# Sheet1.net
KiCad netlist of a schematic drawn in Altium Designer
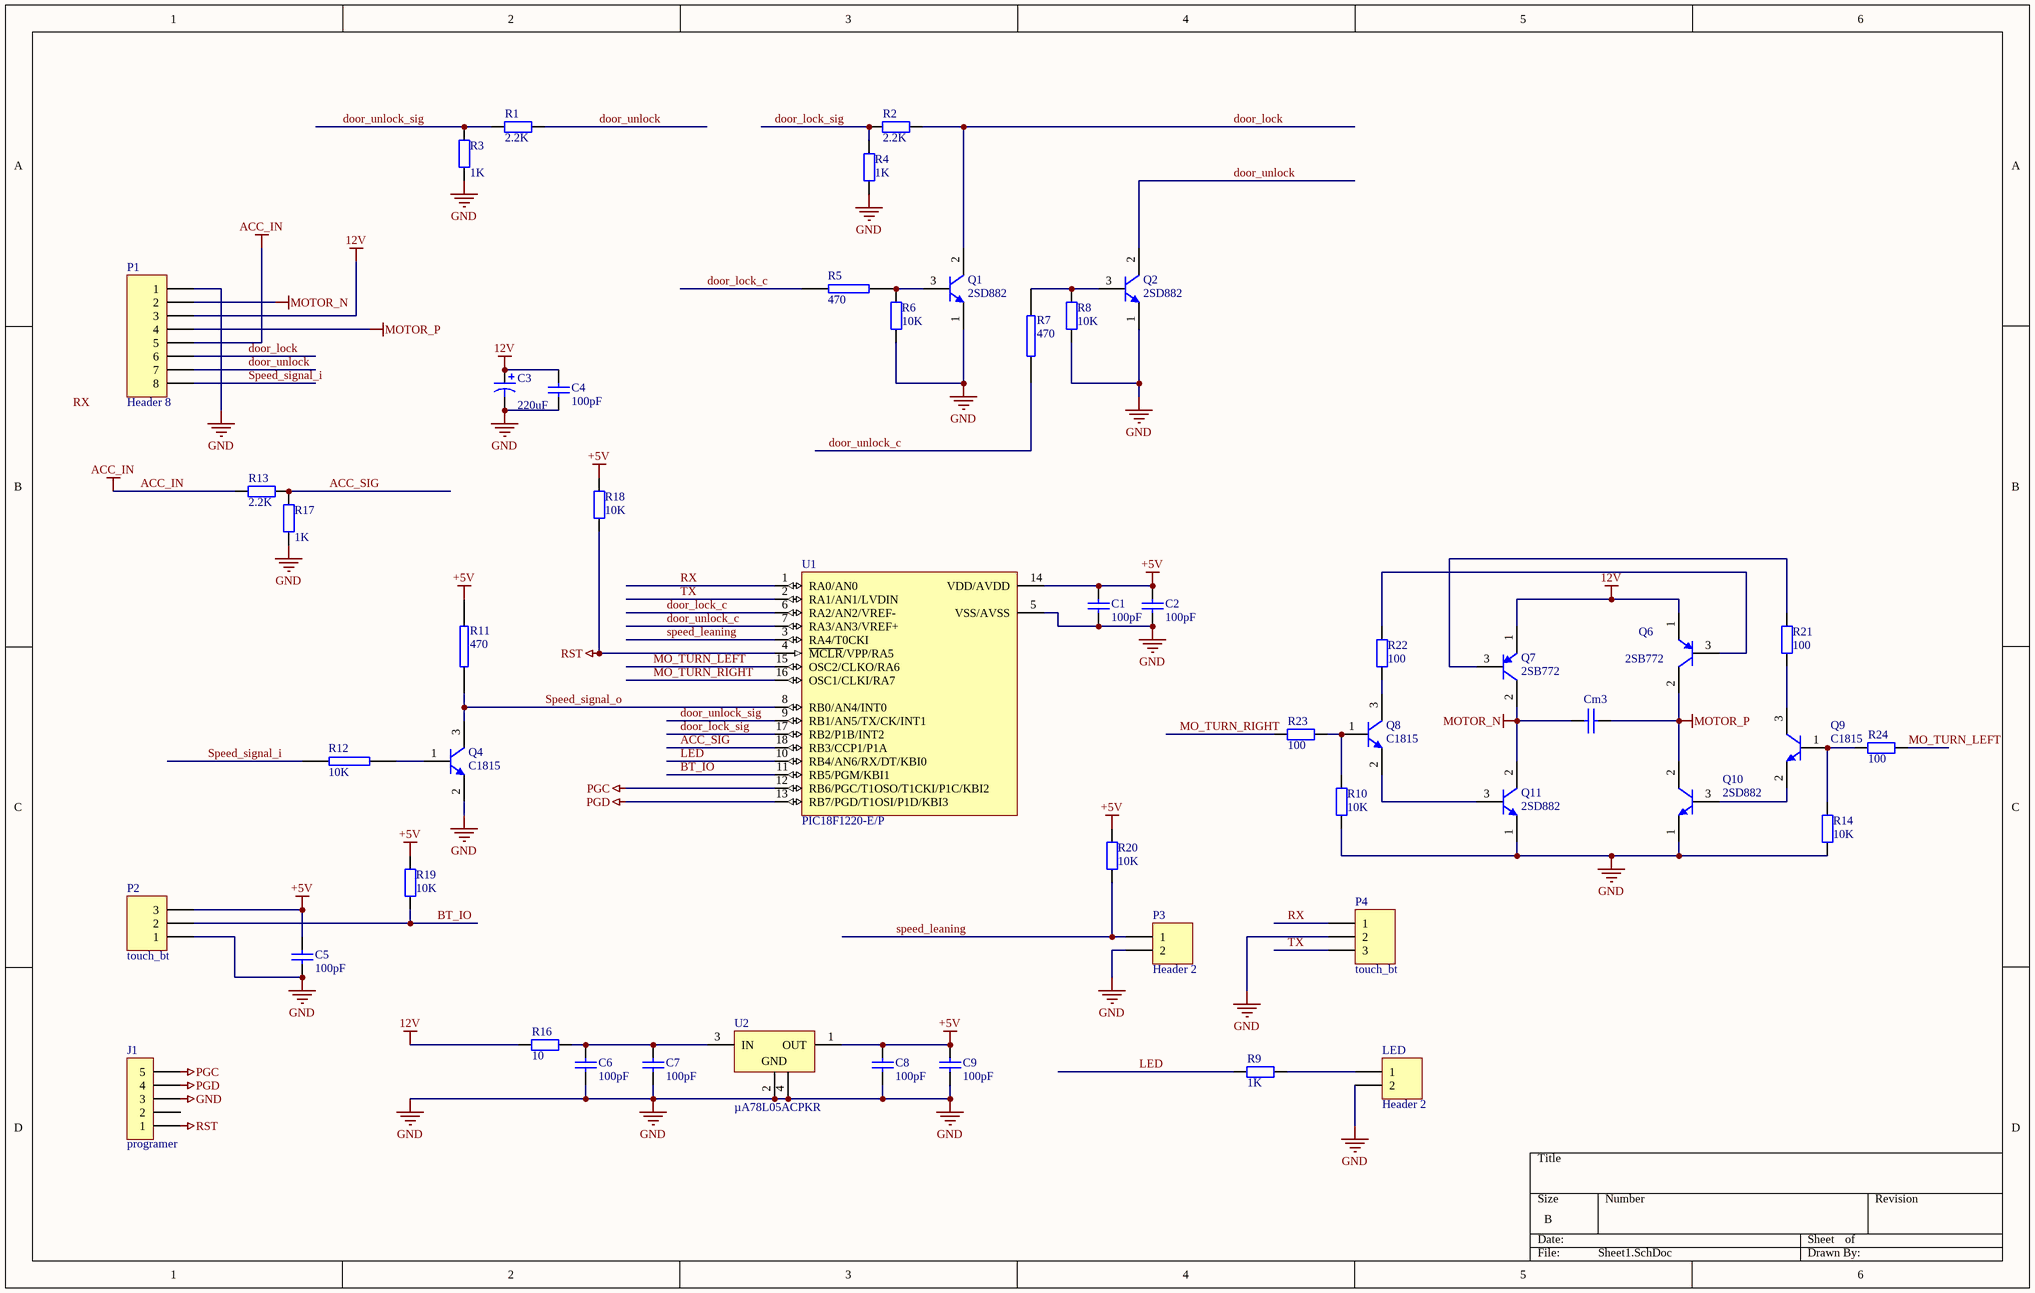
[diagram p0: Sheet1.SchDoc]

(export (version "E")
  (design (tool "Eeschema 10.0.6"))
  (components
    (comp (ref "C1")
      (value "100pF")
      (footprint "RESC2012L")
      (description "Capacitor (Semiconductor SIM Model)")
      (fields (field (name "Comment") "Cap Semi") (field (name "PUBLISHER") "Altium Limited"))
      (libsource (lib "Miscellaneous Devices") (part "Cap Semi"))
    )
    (comp (ref "C2")
      (value "100pF")
      (footprint "RESC2012L")
      (description "Capacitor (Semiconductor SIM Model)")
      (fields (field (name "Comment") "Cap Semi") (field (name "PUBLISHER") "Altium Limited"))
      (libsource (lib "Miscellaneous Devices") (part "Cap Semi"))
    )
    (comp (ref "C3")
      (value "220uF")
      (footprint "CAPU150-175K")
      (description "Polarized Capacitor (Surface Mount)")
      (fields (field (name "Comment") "Cap Pol3") (field (name "PUBLISHER") "Altium Limited"))
      (libsource (lib "Miscellaneous Devices") (part "Cap Pol3"))
    )
    (comp (ref "C4")
      (value "100pF")
      (footprint "RESC2012L")
      (description "Capacitor (Semiconductor SIM Model)")
      (fields (field (name "Comment") "Cap Semi") (field (name "PUBLISHER") "Altium Limited"))
      (libsource (lib "Miscellaneous Devices") (part "Cap Semi"))
    )
    (comp (ref "C5")
      (value "100pF")
      (footprint "RESC2012L")
      (description "Capacitor (Semiconductor SIM Model)")
      (fields (field (name "Comment") "Cap Semi") (field (name "PUBLISHER") "Altium Limited"))
      (libsource (lib "Miscellaneous Devices") (part "Cap Semi"))
    )
    (comp (ref "C6")
      (value "100pF")
      (footprint "RESC2012L")
      (description "Capacitor (Semiconductor SIM Model)")
      (fields (field (name "Comment") "Cap Semi") (field (name "PUBLISHER") "Altium Limited"))
      (libsource (lib "Miscellaneous Devices") (part "Cap Semi"))
    )
    (comp (ref "C7")
      (value "100pF")
      (footprint "RESC2012L")
      (description "Capacitor (Semiconductor SIM Model)")
      (fields (field (name "Comment") "Cap Semi") (field (name "PUBLISHER") "Altium Limited"))
      (libsource (lib "Miscellaneous Devices") (part "Cap Semi"))
    )
    (comp (ref "C8")
      (value "100pF")
      (footprint "RESC2012L")
      (description "Capacitor (Semiconductor SIM Model)")
      (fields (field (name "Comment") "Cap Semi") (field (name "PUBLISHER") "Altium Limited"))
      (libsource (lib "Miscellaneous Devices") (part "Cap Semi"))
    )
    (comp (ref "C9")
      (value "100pF")
      (footprint "RESC2012L")
      (description "Capacitor (Semiconductor SIM Model)")
      (fields (field (name "Comment") "Cap Semi") (field (name "PUBLISHER") "Altium Limited"))
      (libsource (lib "Miscellaneous Devices") (part "Cap Semi"))
    )
    (comp (ref "Cm3")
      (value "~")
      (footprint "1206")
      (description "Capacitor")
      (libsource (lib "*") (part "CAP"))
    )
    (comp (ref "J1")
      (value "programer")
      (footprint "HDR1x5")
      (description "Connector")
      (libsource (lib "*") (part "CON5"))
    )
    (comp (ref "LED")
      (value "Header 2")
      (footprint "HDR1X2")
      (description "Header, 2-Pin")
      (fields (field (name "PUBLISHER") "Altium Limited"))
      (libsource (lib "Miscellaneous Connectors") (part "Header 2"))
    )
    (comp (ref "P1")
      (value "Header 8")
      (footprint "P8_150")
      (description "Header, 8-Pin")
      (fields (field (name "PUBLISHER") "Altium Limited"))
      (libsource (lib "Miscellaneous Connectors") (part "Header 8"))
    )
    (comp (ref "P2")
      (value "touch_bt")
      (footprint "HDR1X3")
      (description "Header, 3-Pin")
      (fields (field (name "PUBLISHER") "Altium Limited"))
      (libsource (lib "Miscellaneous Connectors") (part "Header 3"))
    )
    (comp (ref "P3")
      (value "Header 2")
      (footprint "HDR1X2")
      (description "Header, 2-Pin")
      (fields (field (name "PUBLISHER") "Altium Limited"))
      (libsource (lib "Miscellaneous Connectors") (part "Header 2"))
    )
    (comp (ref "P4")
      (value "touch_bt")
      (footprint "HDR1X3")
      (description "Header, 3-Pin")
      (fields (field (name "PUBLISHER") "Altium Limited"))
      (libsource (lib "") (part "Header 3_1"))
    )
    (comp (ref "Q1")
      (value "2SD882")
      (footprint "ONSC-TO-225-3-77-09")
      (description "Plastic Medium-Power NPN Silicon Transistor, 3-Pin TO-225, Bulk Box")
      (fields (field (name "MANUFACTURER") "On Semiconductor") (field (name "PARTNUMBER") "MJE340"))
      (libsource (lib "ON Semi General Purpose Transistors") (part "MJE340"))
    )
    (comp (ref "Q2")
      (value "2SD882")
      (footprint "ONSC-TO-225-3-77-09")
      (description "Plastic Medium-Power NPN Silicon Transistor, 3-Pin TO-225, Bulk Box")
      (fields (field (name "MANUFACTURER") "On Semiconductor") (field (name "PARTNUMBER") "MJE340"))
      (libsource (lib "ON Semi General Purpose Transistors") (part "MJE340"))
    )
    (comp (ref "Q4")
      (value "C1815")
      (footprint "ONSC-CPA-3_V")
      (description "Bipolar Transistor, 50 V, 150 mA, Low VCE(sat), NPN Single, 3-Pin CPA, Pb-Free, Tape and Reel")
      (fields
        (field (name "MANUFACTURER") "On Semiconductor")
        (field (name "PARTNUMBER") "2SC2812N6-CPA-TB-E")
      )
      (libsource (lib "ON Semi General Purpose Transistors") (part "2SC2812N6-CPA-TB-E"))
    )
    (comp (ref "Q6")
      (value "2SB772")
      (footprint "ONSC-TO-225-3-77-09")
      (description "Plastic Medium-Power PNP Silicon Transistor, 3-Pin TO-225, Bulk Box")
      (fields (field (name "MANUFACTURER") "On Semiconductor") (field (name "PARTNUMBER") "MJE350"))
      (libsource (lib "ON Semi General Purpose Transistors") (part "MJE350"))
    )
    (comp (ref "Q7")
      (value "2SB772")
      (footprint "ONSC-TO-225-3-77-09")
      (description "Plastic Medium-Power PNP Silicon Transistor, 3-Pin TO-225, Bulk Box")
      (fields (field (name "MANUFACTURER") "On Semiconductor") (field (name "PARTNUMBER") "MJE350"))
      (libsource (lib "ON Semi General Purpose Transistors") (part "MJE350"))
    )
    (comp (ref "Q8")
      (value "C1815")
      (footprint "ONSC-CPA-3_V")
      (description "Bipolar Transistor, 50 V, 150 mA, Low VCE(sat), NPN Single, 3-Pin CPA, Pb-Free, Tape and Reel")
      (fields
        (field (name "MANUFACTURER") "On Semiconductor")
        (field (name "PARTNUMBER") "2SC2812N6-CPA-TB-E")
      )
      (libsource (lib "ON Semi General Purpose Transistors") (part "2SC2812N6-CPA-TB-E"))
    )
    (comp (ref "Q9")
      (value "C1815")
      (footprint "ONSC-CPA-3_V")
      (description "Bipolar Transistor, 50 V, 150 mA, Low VCE(sat), NPN Single, 3-Pin CPA, Pb-Free, Tape and Reel")
      (fields
        (field (name "MANUFACTURER") "On Semiconductor")
        (field (name "PARTNUMBER") "2SC2812N6-CPA-TB-E")
      )
      (libsource (lib "ON Semi General Purpose Transistors") (part "2SC2812N6-CPA-TB-E"))
    )
    (comp (ref "Q10")
      (value "2SD882")
      (footprint "ONSC-TO-225-3-77-09")
      (description "Plastic Medium-Power NPN Silicon Transistor, 3-Pin TO-225, Bulk Box")
      (fields (field (name "MANUFACTURER") "On Semiconductor") (field (name "PARTNUMBER") "MJE340"))
      (libsource (lib "ON Semi General Purpose Transistors") (part "MJE340"))
    )
    (comp (ref "Q11")
      (value "2SD882")
      (footprint "ONSC-TO-225-3-77-09")
      (description "Plastic Medium-Power NPN Silicon Transistor, 3-Pin TO-225, Bulk Box")
      (fields (field (name "MANUFACTURER") "On Semiconductor") (field (name "PARTNUMBER") "MJE340"))
      (libsource (lib "ON Semi General Purpose Transistors") (part "MJE340"))
    )
    (comp (ref "R1")
      (value "2.2K")
      (footprint "RESC2012L")
      (description "Resistor")
      (fields (field (name "Comment") "Res2") (field (name "PUBLISHER") "Altium Limited"))
      (libsource (lib "") (part "Res2_1"))
    )
    (comp (ref "R2")
      (value "2.2K")
      (footprint "RESC2012L")
      (description "Resistor")
      (fields (field (name "Comment") "Res2") (field (name "PUBLISHER") "Altium Limited"))
      (libsource (lib "") (part "Res2_1"))
    )
    (comp (ref "R3")
      (value "1K")
      (footprint "RESC2012L")
      (description "Resistor")
      (fields (field (name "Comment") "Res2") (field (name "PUBLISHER") "Altium Limited"))
      (libsource (lib "") (part "Res2_2"))
    )
    (comp (ref "R4")
      (value "1K")
      (footprint "RESC2012L")
      (description "Resistor")
      (fields (field (name "Comment") "Res2") (field (name "PUBLISHER") "Altium Limited"))
      (libsource (lib "Miscellaneous Devices") (part "Res2"))
    )
    (comp (ref "R5") (value "470") (footprint "RESC2012L") (libsource (lib "*") (part "RES2")))
    (comp (ref "R6")
      (value "10K")
      (footprint "RESC2012L")
      (description "Resistor")
      (fields (field (name "Comment") "Res2") (field (name "PUBLISHER") "Altium Limited"))
      (libsource (lib "Miscellaneous Devices") (part "Res2"))
    )
    (comp (ref "R7") (value "470") (footprint "RESC2012L") (libsource (lib "*") (part "RES2")))
    (comp (ref "R8")
      (value "10K")
      (footprint "RESC2012L")
      (description "Resistor")
      (fields (field (name "Comment") "Res2") (field (name "PUBLISHER") "Altium Limited"))
      (libsource (lib "Miscellaneous Devices") (part "Res2"))
    )
    (comp (ref "R9")
      (value "1K")
      (footprint "RESC2012L")
      (description "Resistor")
      (fields (field (name "Comment") "Res2") (field (name "PUBLISHER") "Altium Limited"))
      (libsource (lib "") (part "Res2_1"))
    )
    (comp (ref "R10")
      (value "10K")
      (footprint "RESC2012L")
      (description "Resistor")
      (fields (field (name "Comment") "Res2") (field (name "PUBLISHER") "Altium Limited"))
      (libsource (lib "Miscellaneous Devices") (part "Res2"))
    )
    (comp (ref "R11") (value "470") (footprint "RESC2012L") (libsource (lib "*") (part "RES2")))
    (comp (ref "R12") (value "10K") (footprint "RESC2012L") (libsource (lib "*") (part "RES2")))
    (comp (ref "R13")
      (value "2.2K")
      (footprint "RESC2012L")
      (description "Resistor")
      (fields (field (name "Comment") "Res2") (field (name "PUBLISHER") "Altium Limited"))
      (libsource (lib "") (part "Res2_1"))
    )
    (comp (ref "R14")
      (value "10K")
      (footprint "RESC2012L")
      (description "Resistor")
      (fields (field (name "Comment") "Res2") (field (name "PUBLISHER") "Altium Limited"))
      (libsource (lib "Miscellaneous Devices") (part "Res2"))
    )
    (comp (ref "R16")
      (value "10")
      (footprint "1206")
      (description "Resistor")
      (fields (field (name "Comment") "Res2") (field (name "PUBLISHER") "Altium Limited"))
      (libsource (lib "") (part "Res2_1"))
    )
    (comp (ref "R17")
      (value "1K")
      (footprint "RESC2012L")
      (description "Resistor")
      (fields (field (name "Comment") "Res2") (field (name "PUBLISHER") "Altium Limited"))
      (libsource (lib "") (part "Res2_2"))
    )
    (comp (ref "R18")
      (value "10K")
      (footprint "RESC2012L")
      (description "Resistor")
      (fields (field (name "Comment") "Res2") (field (name "PUBLISHER") "Altium Limited"))
      (libsource (lib "Miscellaneous Devices") (part "Res2"))
    )
    (comp (ref "R19")
      (value "10K")
      (footprint "RESC2012L")
      (description "Resistor")
      (fields (field (name "Comment") "Res2") (field (name "PUBLISHER") "Altium Limited"))
      (libsource (lib "Miscellaneous Devices") (part "Res2"))
    )
    (comp (ref "R20")
      (value "10K")
      (footprint "RESC2012L")
      (description "Resistor")
      (fields (field (name "Comment") "Res2") (field (name "PUBLISHER") "Altium Limited"))
      (libsource (lib "Miscellaneous Devices") (part "Res2"))
    )
    (comp (ref "R21")
      (value "100")
      (footprint "RESC2012L")
      (description "Resistor")
      (fields (field (name "Comment") "Res2") (field (name "PUBLISHER") "Altium Limited"))
      (libsource (lib "Miscellaneous Devices") (part "Res2"))
    )
    (comp (ref "R22")
      (value "100")
      (footprint "RESC2012L")
      (description "Resistor")
      (fields (field (name "Comment") "Res2") (field (name "PUBLISHER") "Altium Limited"))
      (libsource (lib "Miscellaneous Devices") (part "Res2"))
    )
    (comp (ref "R23")
      (value "100")
      (footprint "RESC2012L")
      (description "Resistor")
      (fields (field (name "Comment") "Res2") (field (name "PUBLISHER") "Altium Limited"))
      (libsource (lib "") (part "Res2_3"))
    )
    (comp (ref "R24")
      (value "100")
      (footprint "RESC2012L")
      (description "Resistor")
      (fields (field (name "Comment") "Res2") (field (name "PUBLISHER") "Altium Limited"))
      (libsource (lib "") (part "Res2_3"))
    )
    (comp (ref "U1")
      (value "PIC18F1220-E/P")
      (footprint "PDIP300-P18")
      (fields (field (name "PUBLISHER") "Altium Limited"))
      (libsource (lib "Microchip Microcontroller 8-Bit PIC18") (part "PIC18F1220-E/P"))
    )
    (comp (ref "U2")
      (value "µA78L05ACPKR")
      (footprint "PK03")
      (description "Positive-Voltage Regulator")
      (fields (field (name "PUBLISHER") "Altium Limited"))
      (libsource (lib "Schlib1") (part "µA78L05ACPKR"))
    )
  )
  (nets
    (net (code "1") (name "+5V") (class "Default")
      (node (ref "C1") (pin "2") (pinfunction "2_2") (pintype "passive"))
      (node (ref "C2") (pin "2") (pinfunction "2_2") (pintype "passive"))
      (node (ref "C5") (pin "2") (pinfunction "2_2") (pintype "passive"))
      (node (ref "C8") (pin "2") (pinfunction "2_2") (pintype "passive"))
      (node (ref "C9") (pin "2") (pinfunction "2_2") (pintype "passive"))
      (node (ref "P2") (pin "3") (pinfunction "3_3") (pintype "passive"))
      (node (ref "R11") (pin "1") (pinfunction "1_1") (pintype "passive"))
      (node (ref "R18") (pin "1") (pinfunction "1_1") (pintype "passive"))
      (node (ref "R19") (pin "1") (pinfunction "1_1") (pintype "passive"))
      (node (ref "R20") (pin "1") (pinfunction "1_1") (pintype "passive"))
      (node (ref "U1") (pin "14") (pinfunction "VDD/AVDD_14") (pintype "power_in"))
      (node (ref "U2") (pin "1") (pinfunction "OUT_1") (pintype "power_in"))
    )
    (net (code "2") (name "/ACC_SIG") (class "Default")
      (node (ref "R13") (pin "1") (pinfunction "1_1") (pintype "passive"))
      (node (ref "R17") (pin "2") (pinfunction "2_2") (pintype "passive"))
      (node (ref "U1") (pin "18") (pinfunction "RB3/CCP1/P1A_18") (pintype "bidirectional"))
    )
    (net (code "3") (name "/BT_IO") (class "Default")
      (node (ref "P2") (pin "2") (pinfunction "2_2") (pintype "passive"))
      (node (ref "R19") (pin "2") (pinfunction "2_2") (pintype "passive"))
      (node (ref "U1") (pin "11") (pinfunction "RB5/PGM/KBI1_11") (pintype "bidirectional"))
    )
    (net (code "4") (name "/LED") (class "Default")
      (node (ref "R9") (pin "2") (pinfunction "2_2") (pintype "passive"))
      (node (ref "U1") (pin "10") (pinfunction "RB4/AN6/RX/DT/KBI0_10") (pintype "bidirectional"))
    )
    (net (code "5") (name "/MO_TURN_LEFT") (class "Default")
      (node (ref "R24") (pin "2") (pinfunction "2_2") (pintype "passive"))
      (node (ref "U1") (pin "15") (pinfunction "OSC2/CLKO/RA6_15") (pintype "bidirectional"))
    )
    (net (code "6") (name "/MO_TURN_RIGHT") (class "Default")
      (node (ref "R23") (pin "1") (pinfunction "1_1") (pintype "passive"))
      (node (ref "U1") (pin "16") (pinfunction "OSC1/CLKI/RA7_16") (pintype "bidirectional"))
    )
    (net (code "7") (name "/RX") (class "Default")
      (node (ref "P4") (pin "1") (pinfunction "1_1") (pintype "passive"))
      (node (ref "U1") (pin "1") (pinfunction "RA0/AN0_1") (pintype "bidirectional"))
    )
    (net (code "8") (name "/Speed_signal_i") (class "Default")
      (node (ref "P1") (pin "8") (pinfunction "8_8") (pintype "passive"))
      (node (ref "R12") (pin "1") (pinfunction "1_1") (pintype "passive"))
    )
    (net (code "9") (name "/Speed_signal_o") (class "Default")
      (node (ref "Q4") (pin "3") (pinfunction "C_3") (pintype "passive"))
      (node (ref "R11") (pin "2") (pinfunction "2_2") (pintype "passive"))
      (node (ref "U1") (pin "8") (pinfunction "RB0/AN4/INT0_8") (pintype "bidirectional"))
    )
    (net (code "10") (name "/TX") (class "Default")
      (node (ref "P4") (pin "3") (pinfunction "3_3") (pintype "passive"))
      (node (ref "U1") (pin "2") (pinfunction "RA1/AN1/LVDIN_2") (pintype "bidirectional"))
    )
    (net (code "11") (name "/door_lock") (class "Default")
      (node (ref "P1") (pin "6") (pinfunction "6_6") (pintype "passive"))
      (node (ref "Q1") (pin "2") (pinfunction "C_2") (pintype "passive"))
      (node (ref "R2") (pin "1") (pinfunction "1_1") (pintype "passive"))
    )
    (net (code "12") (name "/door_lock_c") (class "Default")
      (node (ref "R5") (pin "1") (pinfunction "1_1") (pintype "passive"))
      (node (ref "U1") (pin "6") (pinfunction "RA2/AN2/VREF-_6") (pintype "bidirectional"))
    )
    (net (code "13") (name "/door_lock_sig") (class "Default")
      (node (ref "R2") (pin "2") (pinfunction "2_2") (pintype "passive"))
      (node (ref "R4") (pin "1") (pinfunction "1_1") (pintype "passive"))
      (node (ref "U1") (pin "17") (pinfunction "RB2/P1B/INT2_17") (pintype "bidirectional"))
    )
    (net (code "14") (name "/door_unlock") (class "Default")
      (node (ref "P1") (pin "7") (pinfunction "7_7") (pintype "passive"))
      (node (ref "Q2") (pin "2") (pinfunction "C_2") (pintype "passive"))
      (node (ref "R1") (pin "1") (pinfunction "1_1") (pintype "passive"))
    )
    (net (code "15") (name "/door_unlock_c") (class "Default")
      (node (ref "R7") (pin "2") (pinfunction "2_2") (pintype "passive"))
      (node (ref "U1") (pin "7") (pinfunction "RA3/AN3/VREF+_7") (pintype "bidirectional"))
    )
    (net (code "16") (name "/door_unlock_sig") (class "Default")
      (node (ref "R1") (pin "2") (pinfunction "2_2") (pintype "passive"))
      (node (ref "R3") (pin "2") (pinfunction "2_2") (pintype "passive"))
      (node (ref "U1") (pin "9") (pinfunction "RB1/AN5/TX/CK/INT1_9") (pintype "bidirectional"))
    )
    (net (code "17") (name "/speed_leaning") (class "Default")
      (node (ref "P3") (pin "1") (pinfunction "1_1") (pintype "passive"))
      (node (ref "R20") (pin "2") (pinfunction "2_2") (pintype "passive"))
      (node (ref "U1") (pin "3") (pinfunction "RA4/T0CKI_3") (pintype "bidirectional"))
    )
    (net (code "18") (name "12V") (class "Default")
      (node (ref "C3") (pin "1") (pinfunction "1_1") (pintype "passive"))
      (node (ref "C4") (pin "2") (pinfunction "2_2") (pintype "passive"))
      (node (ref "P1") (pin "3") (pinfunction "3_3") (pintype "passive"))
      (node (ref "Q6") (pin "1") (pinfunction "E_1") (pintype "passive"))
      (node (ref "Q7") (pin "1") (pinfunction "E_1") (pintype "passive"))
      (node (ref "R16") (pin "2") (pinfunction "2_2") (pintype "passive"))
    )
    (net (code "19") (name "ACC_IN") (class "Default")
      (node (ref "P1") (pin "5") (pinfunction "5_5") (pintype "passive"))
      (node (ref "R13") (pin "2") (pinfunction "2_2") (pintype "passive"))
    )
    (net (code "20") (name "GND") (class "Default")
      (node (ref "C1") (pin "1") (pinfunction "1_1") (pintype "passive"))
      (node (ref "C2") (pin "1") (pinfunction "1_1") (pintype "passive"))
      (node (ref "C3") (pin "2") (pinfunction "2_2") (pintype "passive"))
      (node (ref "C4") (pin "1") (pinfunction "1_1") (pintype "passive"))
      (node (ref "C5") (pin "1") (pinfunction "1_1") (pintype "passive"))
      (node (ref "C6") (pin "1") (pinfunction "1_1") (pintype "passive"))
      (node (ref "C7") (pin "1") (pinfunction "1_1") (pintype "passive"))
      (node (ref "C8") (pin "1") (pinfunction "1_1") (pintype "passive"))
      (node (ref "C9") (pin "1") (pinfunction "1_1") (pintype "passive"))
      (node (ref "J1") (pin "3") (pinfunction "3_3") (pintype "passive"))
      (node (ref "LED") (pin "2") (pinfunction "2_2") (pintype "passive"))
      (node (ref "P1") (pin "1") (pinfunction "1_1") (pintype "passive"))
      (node (ref "P2") (pin "1") (pinfunction "1_1") (pintype "passive"))
      (node (ref "P3") (pin "2") (pinfunction "2_2") (pintype "passive"))
      (node (ref "P4") (pin "2") (pinfunction "2_2") (pintype "passive"))
      (node (ref "Q1") (pin "1") (pinfunction "E_1") (pintype "passive"))
      (node (ref "Q10") (pin "1") (pinfunction "E_1") (pintype "passive"))
      (node (ref "Q11") (pin "1") (pinfunction "E_1") (pintype "passive"))
      (node (ref "Q2") (pin "1") (pinfunction "E_1") (pintype "passive"))
      (node (ref "Q4") (pin "2") (pinfunction "E_2") (pintype "passive"))
      (node (ref "R10") (pin "2") (pinfunction "2_2") (pintype "passive"))
      (node (ref "R14") (pin "2") (pinfunction "2_2") (pintype "passive"))
      (node (ref "R17") (pin "1") (pinfunction "1_1") (pintype "passive"))
      (node (ref "R3") (pin "1") (pinfunction "1_1") (pintype "passive"))
      (node (ref "R4") (pin "2") (pinfunction "2_2") (pintype "passive"))
      (node (ref "R6") (pin "2") (pinfunction "2_2") (pintype "passive"))
      (node (ref "R8") (pin "2") (pinfunction "2_2") (pintype "passive"))
      (node (ref "U1") (pin "5") (pinfunction "VSS/AVSS_5") (pintype "power_in"))
      (node (ref "U2") (pin "2") (pinfunction "GND_2") (pintype "power_in"))
      (node (ref "U2") (pin "4") (pinfunction "GND_4") (pintype "power_in"))
    )
    (net (code "21") (name "MOTOR_N") (class "Default")
      (node (ref "Cm3") (pin "1") (pinfunction "1_1") (pintype "passive"))
      (node (ref "P1") (pin "2") (pinfunction "2_2") (pintype "passive"))
      (node (ref "Q11") (pin "2") (pinfunction "C_2") (pintype "passive"))
      (node (ref "Q7") (pin "2") (pinfunction "C_2") (pintype "passive"))
    )
    (net (code "22") (name "MOTOR_P") (class "Default")
      (node (ref "Cm3") (pin "2") (pinfunction "2_2") (pintype "passive"))
      (node (ref "P1") (pin "4") (pinfunction "4_4") (pintype "passive"))
      (node (ref "Q10") (pin "2") (pinfunction "C_2") (pintype "passive"))
      (node (ref "Q6") (pin "2") (pinfunction "C_2") (pintype "passive"))
    )
    (net (code "23") (name "Net-(LED-Pad1)") (class "Default")
      (node (ref "LED") (pin "1") (pinfunction "1_1") (pintype "passive"))
      (node (ref "R9") (pin "1") (pinfunction "1_1") (pintype "passive"))
    )
    (net (code "24") (name "Net-(Q1-B)") (class "Default")
      (node (ref "Q1") (pin "3") (pinfunction "B_3") (pintype "passive"))
      (node (ref "R5") (pin "2") (pinfunction "2_2") (pintype "passive"))
      (node (ref "R6") (pin "1") (pinfunction "1_1") (pintype "passive"))
    )
    (net (code "25") (name "Net-(Q2-B)") (class "Default")
      (node (ref "Q2") (pin "3") (pinfunction "B_3") (pintype "passive"))
      (node (ref "R7") (pin "1") (pinfunction "1_1") (pintype "passive"))
      (node (ref "R8") (pin "1") (pinfunction "1_1") (pintype "passive"))
    )
    (net (code "26") (name "Net-(Q4-B)") (class "Default")
      (node (ref "Q4") (pin "1") (pinfunction "B_1") (pintype "passive"))
      (node (ref "R12") (pin "2") (pinfunction "2_2") (pintype "passive"))
    )
    (net (code "27") (name "Net-(Q6-B)") (class "Default")
      (node (ref "Q6") (pin "3") (pinfunction "B_3") (pintype "passive"))
      (node (ref "R22") (pin "1") (pinfunction "1_1") (pintype "passive"))
    )
    (net (code "28") (name "Net-(Q7-B)") (class "Default")
      (node (ref "Q7") (pin "3") (pinfunction "B_3") (pintype "passive"))
      (node (ref "R21") (pin "1") (pinfunction "1_1") (pintype "passive"))
    )
    (net (code "29") (name "Net-(Q8-B)") (class "Default")
      (node (ref "Q8") (pin "1") (pinfunction "B_1") (pintype "passive"))
      (node (ref "R10") (pin "1") (pinfunction "1_1") (pintype "passive"))
      (node (ref "R23") (pin "2") (pinfunction "2_2") (pintype "passive"))
    )
    (net (code "30") (name "Net-(Q8-C)") (class "Default")
      (node (ref "Q8") (pin "3") (pinfunction "C_3") (pintype "passive"))
      (node (ref "R22") (pin "2") (pinfunction "2_2") (pintype "passive"))
    )
    (net (code "31") (name "Net-(Q9-B)") (class "Default")
      (node (ref "Q9") (pin "1") (pinfunction "B_1") (pintype "passive"))
      (node (ref "R14") (pin "1") (pinfunction "1_1") (pintype "passive"))
      (node (ref "R24") (pin "1") (pinfunction "1_1") (pintype "passive"))
    )
    (net (code "32") (name "Net-(Q9-C)") (class "Default")
      (node (ref "Q9") (pin "3") (pinfunction "C_3") (pintype "passive"))
      (node (ref "R21") (pin "2") (pinfunction "2_2") (pintype "passive"))
    )
    (net (code "33") (name "Net-(Q10-B)") (class "Default")
      (node (ref "Q10") (pin "3") (pinfunction "B_3") (pintype "passive"))
      (node (ref "Q9") (pin "2") (pinfunction "E_2") (pintype "passive"))
    )
    (net (code "34") (name "Net-(Q11-B)") (class "Default")
      (node (ref "Q11") (pin "3") (pinfunction "B_3") (pintype "passive"))
      (node (ref "Q8") (pin "2") (pinfunction "E_2") (pintype "passive"))
    )
    (net (code "35") (name "Net-(U2-IN)") (class "Default")
      (node (ref "C6") (pin "2") (pinfunction "2_2") (pintype "passive"))
      (node (ref "C7") (pin "2") (pinfunction "2_2") (pintype "passive"))
      (node (ref "R16") (pin "1") (pinfunction "1_1") (pintype "passive"))
      (node (ref "U2") (pin "3") (pinfunction "IN_3") (pintype "power_in"))
    )
    (net (code "36") (name "PGC") (class "Default")
      (node (ref "J1") (pin "5") (pinfunction "5_5") (pintype "passive"))
      (node (ref "U1") (pin "12") (pinfunction "RB6/PGC/T1OSO/T1CKI/P1C/KBI2_12") (pintype "bidirectional"))
    )
    (net (code "37") (name "PGD") (class "Default")
      (node (ref "J1") (pin "4") (pinfunction "4_4") (pintype "passive"))
      (node (ref "U1") (pin "13") (pinfunction "RB7/PGD/T1OSI/P1D/KBI3_13") (pintype "bidirectional"))
    )
    (net (code "38") (name "RST") (class "Default")
      (node (ref "J1") (pin "1") (pinfunction "1_1") (pintype "passive"))
      (node (ref "R18") (pin "2") (pinfunction "2_2") (pintype "passive"))
      (node (ref "U1") (pin "4") (pinfunction "~{MCLR}/VPP/RA5_4") (pintype "input"))
    )
    (net (code "39") (name "unconnected-(J1-Pad2)") (class "Default")
      (node (ref "J1") (pin "2") (pinfunction "2_2") (pintype "passive"))
    )
  )
)
